# ESP-D1-mini-mainboard.net
KiCad netlist of a schematic drawn in EAGLE
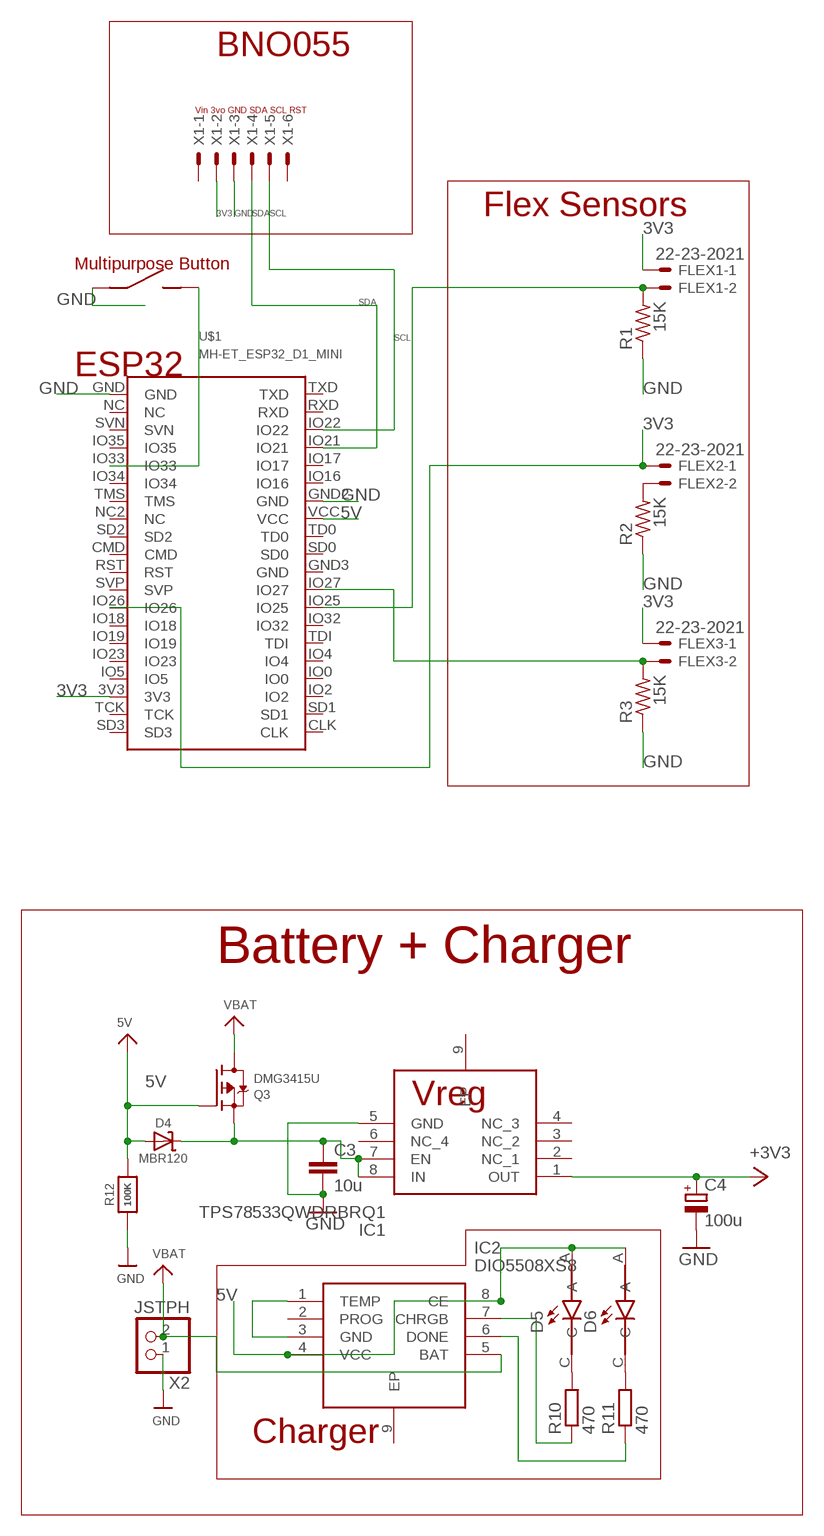
[diagram p0: schematic, sheet 1]

(export (version "E")
  (design (tool "Eeschema 10.0.6"))
  (components
    (comp (ref "BTN2")
      (value "TS36CA-0.7")
      (footprint "eagle-import:SMD")
      (fields (field (name "MF") "SHOU HAN"))
      (libsource (lib "eagle-import") (part "TS36CA-0.7"))
    )
    (comp (ref "C3")
      (value "10u")
      (footprint "eagle-import:C0603")
      (libsource (lib "eagle-import") (part "C-EUC0603"))
    )
    (comp (ref "C4")
      (value "100u")
      (footprint "eagle-import:B_3528-21W")
      (libsource (lib "eagle-import") (part "CPOL-EUB/3528-21W"))
    )
    (comp (ref "D4")
      (value "MBR120")
      (footprint "eagle-import:SOD-123")
      (libsource (lib "eagle-import") (part "DIODE-SCHOTTKYSOD-123"))
    )
    (comp (ref "D5")
      (value "GREEN")
      (footprint "eagle-import:LEDC2012X70N")
      (fields (field (name "MF") "Dialight") (field (name "MP") "597-5311-402F"))
      (libsource (lib "eagle-import") (part "597-5311-402F"))
    )
    (comp (ref "D6")
      (value "GREEN")
      (footprint "eagle-import:LEDC2012X70N")
      (fields (field (name "MF") "Dialight") (field (name "MP") "597-5311-402F"))
      (libsource (lib "eagle-import") (part "597-5311-402F"))
    )
    (comp (ref "FLEX1")
      (value "22-23-2021")
      (footprint "eagle-import:22-23-2021")
      (fields (field (name "MF") "MOLEX"))
      (libsource (lib "eagle-import") (part "22-23-2021"))
    )
    (comp (ref "FLEX2")
      (value "22-23-2021")
      (footprint "eagle-import:22-23-2021")
      (fields (field (name "MF") "MOLEX"))
      (libsource (lib "eagle-import") (part "22-23-2021"))
    )
    (comp (ref "FLEX3")
      (value "22-23-2021")
      (footprint "eagle-import:22-23-2021")
      (fields (field (name "MF") "MOLEX"))
      (libsource (lib "eagle-import") (part "22-23-2021"))
    )
    (comp (ref "IC1")
      (value "TPS78533QWDRBRQ1")
      (footprint "eagle-import:SON65P300X300X100-9N")
      (fields (field (name "MOUSER_PART_NUMBER") "595-TPS78533QWDRBRQ1"))
      (libsource (lib "eagle-import") (part "TPS78533QWDRBRQ1"))
    )
    (comp (ref "IC2")
      (value "DIO5508XS8")
      (footprint "eagle-import:SOIC127P600X170-9N")
      (fields (field (name "MOUSER_PART_NUMBER") "453-DIO5508XS8"))
      (libsource (lib "eagle-import") (part "DIO5508XS8"))
    )
    (comp (ref "Q3")
      (value "DMG3415U")
      (footprint "eagle-import:SOT23-R")
      (libsource (lib "eagle-import") (part "MOSFET-P"))
    )
    (comp (ref "R1")
      (value "15K")
      (footprint "eagle-import:0805-THM")
      (libsource (lib "eagle-import") (part "FLIPFLOP-RES"))
    )
    (comp (ref "R2")
      (value "15K")
      (footprint "eagle-import:0805-THM")
      (libsource (lib "eagle-import") (part "FLIPFLOP-RES"))
    )
    (comp (ref "R3")
      (value "15K")
      (footprint "eagle-import:0805-THM")
      (libsource (lib "eagle-import") (part "FLIPFLOP-RES"))
    )
    (comp (ref "R10")
      (value "470")
      (footprint "eagle-import:R0603")
      (libsource (lib "eagle-import") (part "R-EU_R0603"))
    )
    (comp (ref "R11")
      (value "470")
      (footprint "eagle-import:R0603")
      (libsource (lib "eagle-import") (part "R-EU_R0603"))
    )
    (comp (ref "R12")
      (value "100K")
      (footprint "eagle-import:0603-NO")
      (libsource (lib "eagle-import") (part "RESISTOR_0603_NOOUT"))
    )
    (comp (ref "U$1")
      (value "MH-ET_ESP32_D1_MINI")
      (footprint "eagle-import:MH-ET_ESP32_D1_MINI")
      (libsource (lib "eagle-import") (part "MH-ET_ESP32_D1_MINI"))
    )
    (comp (ref "X1")
      (value "22-23-2061")
      (footprint "eagle-import:22-23-2061")
      (fields (field (name "MF") "MOLEX"))
      (libsource (lib "eagle-import") (part "22-23-2061"))
    )
    (comp (ref "X2")
      (value "JSTPH")
      (footprint "eagle-import:JSTPH2")
      (libsource (lib "eagle-import") (part "CON_JST_PH_2PIN"))
    )
  )
  (nets
    (net (code "1") (name "+3V3") (class "Default")
      (node (ref "C4") (pin "+") (pinfunction "+_+") (pintype "passive"))
      (node (ref "IC1") (pin "1") (pinfunction "OUT_1") (pintype "bidirectional"))
    )
    (net (code "2") (name "/3V3") (class "Default")
      (node (ref "FLEX1") (pin "1") (pinfunction "S_1") (pintype "passive"))
      (node (ref "FLEX2") (pin "1") (pinfunction "S_1") (pintype "passive"))
      (node (ref "FLEX3") (pin "1") (pinfunction "S_1") (pintype "passive"))
      (node (ref "U$1") (pin "3V3") (pinfunction "3V3_3V3") (pintype "bidirectional"))
      (node (ref "U$1") (pin "IO26") (pinfunction "IO26_IO26") (pintype "bidirectional"))
      (node (ref "X1") (pin "2") (pinfunction "S_2") (pintype "passive"))
    )
    (net (code "3") (name "/SCL") (class "Default")
      (node (ref "U$1") (pin "IO22") (pinfunction "IO22_IO22") (pintype "bidirectional"))
      (node (ref "X1") (pin "5") (pinfunction "S_5") (pintype "passive"))
    )
    (net (code "4") (name "/SDA") (class "Default")
      (node (ref "U$1") (pin "IO21") (pinfunction "IO21_IO21") (pintype "bidirectional"))
      (node (ref "X1") (pin "4") (pinfunction "S_4") (pintype "passive"))
    )
    (net (code "5") (name "5V") (class "Default")
      (node (ref "D4") (pin "A") (pinfunction "A_A") (pintype "passive"))
      (node (ref "D5") (pin "A") (pinfunction "A_A") (pintype "passive"))
      (node (ref "D6") (pin "A") (pinfunction "A_A") (pintype "passive"))
      (node (ref "IC2") (pin "4") (pinfunction "VCC_4") (pintype "bidirectional"))
      (node (ref "IC2") (pin "8") (pinfunction "CE_8") (pintype "bidirectional"))
      (node (ref "Q3") (pin "1") (pinfunction "G_1") (pintype "passive"))
      (node (ref "R12") (pin "2") (pinfunction "2_2") (pintype "passive"))
      (node (ref "U$1") (pin "VCC") (pinfunction "VCC_VCC") (pintype "bidirectional"))
    )
    (net (code "6") (name "GND") (class "Default")
      (node (ref "BTN2") (pin "A") (pinfunction "CASE_A") (pintype "power_in"))
      (node (ref "BTN2") (pin "B") (pinfunction "CASE_B") (pintype "power_in"))
      (node (ref "BTN2") (pin "C") (pinfunction "P$1_C") (pintype "bidirectional"))
      (node (ref "C3") (pin "2") (pinfunction "2_2") (pintype "passive"))
      (node (ref "C4") (pin "-") (pinfunction "-_-") (pintype "passive"))
      (node (ref "IC1") (pin "5") (pinfunction "GND_5") (pintype "bidirectional"))
      (node (ref "R1") (pin "1") (pinfunction "1_1") (pintype "passive"))
      (node (ref "R12") (pin "1") (pinfunction "1_1") (pintype "passive"))
      (node (ref "R2") (pin "1") (pinfunction "1_1") (pintype "passive"))
      (node (ref "R3") (pin "1") (pinfunction "1_1") (pintype "passive"))
      (node (ref "U$1") (pin "GND") (pinfunction "GND_GND") (pintype "bidirectional"))
      (node (ref "U$1") (pin "GND2") (pinfunction "GND_GND2") (pintype "bidirectional"))
      (node (ref "X1") (pin "3") (pinfunction "S_3") (pintype "passive"))
      (node (ref "X2") (pin "1") (pinfunction "1_1") (pintype "passive"))
    )
    (net (code "7") (name "Net-(BTN2-P$2)") (class "Default")
      (node (ref "BTN2") (pin "D") (pinfunction "P$2_D") (pintype "bidirectional"))
      (node (ref "U$1") (pin "IO33") (pinfunction "IO33_IO33") (pintype "bidirectional"))
    )
    (net (code "8") (name "Net-(D5-PadC)") (class "Default")
      (node (ref "D5") (pin "C") (pinfunction "C_C") (pintype "passive"))
      (node (ref "R10") (pin "2") (pinfunction "2_2") (pintype "passive"))
    )
    (net (code "9") (name "Net-(D6-PadC)") (class "Default")
      (node (ref "D6") (pin "C") (pinfunction "C_C") (pintype "passive"))
      (node (ref "R11") (pin "2") (pinfunction "2_2") (pintype "passive"))
    )
    (net (code "10") (name "Net-(FLEX1B-S)") (class "Default")
      (node (ref "FLEX1") (pin "2") (pinfunction "S_2") (pintype "passive"))
      (node (ref "R1") (pin "2") (pinfunction "2_2") (pintype "passive"))
      (node (ref "U$1") (pin "IO25") (pinfunction "IO25_IO25") (pintype "bidirectional"))
    )
    (net (code "11") (name "Net-(FLEX2B-S)") (class "Default")
      (node (ref "FLEX2") (pin "2") (pinfunction "S_2") (pintype "passive"))
      (node (ref "R2") (pin "2") (pinfunction "2_2") (pintype "passive"))
    )
    (net (code "12") (name "Net-(FLEX3B-S)") (class "Default")
      (node (ref "FLEX3") (pin "2") (pinfunction "S_2") (pintype "passive"))
      (node (ref "R3") (pin "2") (pinfunction "2_2") (pintype "passive"))
      (node (ref "U$1") (pin "IO27") (pinfunction "IO27_IO27") (pintype "bidirectional"))
    )
    (net (code "13") (name "Net-(IC1-EN)") (class "Default")
      (node (ref "C3") (pin "1") (pinfunction "1_1") (pintype "passive"))
      (node (ref "D4") (pin "C") (pinfunction "C_C") (pintype "passive"))
      (node (ref "IC1") (pin "7") (pinfunction "EN_7") (pintype "bidirectional"))
      (node (ref "IC1") (pin "8") (pinfunction "IN_8") (pintype "bidirectional"))
      (node (ref "Q3") (pin "2") (pinfunction "S_2") (pintype "passive"))
    )
    (net (code "14") (name "Net-(IC2-CHRGB)") (class "Default")
      (node (ref "IC2") (pin "7") (pinfunction "CHRGB_7") (pintype "bidirectional"))
      (node (ref "R10") (pin "1") (pinfunction "1_1") (pintype "passive"))
    )
    (net (code "15") (name "Net-(IC2-DONE)") (class "Default")
      (node (ref "IC2") (pin "6") (pinfunction "DONE_6") (pintype "bidirectional"))
      (node (ref "R11") (pin "1") (pinfunction "1_1") (pintype "passive"))
    )
    (net (code "16") (name "Net-(IC2-GND)") (class "Default")
      (node (ref "IC2") (pin "1") (pinfunction "TEMP_1") (pintype "bidirectional"))
      (node (ref "IC2") (pin "3") (pinfunction "GND_3") (pintype "bidirectional"))
    )
    (net (code "17") (name "VBAT") (class "Default")
      (node (ref "IC2") (pin "5") (pinfunction "BAT_5") (pintype "bidirectional"))
      (node (ref "Q3") (pin "3") (pinfunction "D_3") (pintype "passive"))
      (node (ref "X2") (pin "2") (pinfunction "2_2") (pintype "passive"))
    )
    (net (code "18") (name "unconnected-(IC1-EP-Pad9)") (class "Default")
      (node (ref "IC1") (pin "9") (pinfunction "EP_9") (pintype "bidirectional"))
    )
    (net (code "19") (name "unconnected-(IC1-NC_1-Pad2)") (class "Default")
      (node (ref "IC1") (pin "2") (pinfunction "NC_1_2") (pintype "bidirectional"))
    )
    (net (code "20") (name "unconnected-(IC1-NC_2-Pad3)") (class "Default")
      (node (ref "IC1") (pin "3") (pinfunction "NC_2_3") (pintype "bidirectional"))
    )
    (net (code "21") (name "unconnected-(IC1-NC_3-Pad4)") (class "Default")
      (node (ref "IC1") (pin "4") (pinfunction "NC_3_4") (pintype "bidirectional"))
    )
    (net (code "22") (name "unconnected-(IC1-NC_4-Pad6)") (class "Default")
      (node (ref "IC1") (pin "6") (pinfunction "NC_4_6") (pintype "bidirectional"))
    )
    (net (code "23") (name "unconnected-(IC2-EP-Pad9)") (class "Default")
      (node (ref "IC2") (pin "9") (pinfunction "EP_9") (pintype "bidirectional"))
    )
    (net (code "24") (name "unconnected-(IC2-PROG-Pad2)") (class "Default")
      (node (ref "IC2") (pin "2") (pinfunction "PROG_2") (pintype "bidirectional"))
    )
    (net (code "25") (name "unconnected-(U$1-GND-PadGND3)") (class "Default")
      (node (ref "U$1") (pin "GND3") (pinfunction "GND_GND3") (pintype "bidirectional"))
    )
    (net (code "26") (name "unconnected-(U$1-NC-PadNC2)") (class "Default")
      (node (ref "U$1") (pin "NC2") (pinfunction "NC_NC2") (pintype "bidirectional"))
    )
    (net (code "27") (name "unconnected-(U$1-PadCLK)") (class "Default")
      (node (ref "U$1") (pin "CLK") (pinfunction "CLK_CLK") (pintype "bidirectional"))
    )
    (net (code "28") (name "unconnected-(U$1-PadCMD)") (class "Default")
      (node (ref "U$1") (pin "CMD") (pinfunction "CMD_CMD") (pintype "bidirectional"))
    )
    (net (code "29") (name "unconnected-(U$1-PadIO0)") (class "Default")
      (node (ref "U$1") (pin "IO0") (pinfunction "IO0_IO0") (pintype "bidirectional"))
    )
    (net (code "30") (name "unconnected-(U$1-PadIO2)") (class "Default")
      (node (ref "U$1") (pin "IO2") (pinfunction "IO2_IO2") (pintype "bidirectional"))
    )
    (net (code "31") (name "unconnected-(U$1-PadIO4)") (class "Default")
      (node (ref "U$1") (pin "IO4") (pinfunction "IO4_IO4") (pintype "bidirectional"))
    )
    (net (code "32") (name "unconnected-(U$1-PadIO5)") (class "Default")
      (node (ref "U$1") (pin "IO5") (pinfunction "IO5_IO5") (pintype "bidirectional"))
    )
    (net (code "33") (name "unconnected-(U$1-PadIO16)") (class "Default")
      (node (ref "U$1") (pin "IO16") (pinfunction "IO16_IO16") (pintype "bidirectional"))
    )
    (net (code "34") (name "unconnected-(U$1-PadIO17)") (class "Default")
      (node (ref "U$1") (pin "IO17") (pinfunction "IO17_IO17") (pintype "bidirectional"))
    )
    (net (code "35") (name "unconnected-(U$1-PadIO18)") (class "Default")
      (node (ref "U$1") (pin "IO18") (pinfunction "IO18_IO18") (pintype "bidirectional"))
    )
    (net (code "36") (name "unconnected-(U$1-PadIO19)") (class "Default")
      (node (ref "U$1") (pin "IO19") (pinfunction "IO19_IO19") (pintype "bidirectional"))
    )
    (net (code "37") (name "unconnected-(U$1-PadIO23)") (class "Default")
      (node (ref "U$1") (pin "IO23") (pinfunction "IO23_IO23") (pintype "bidirectional"))
    )
    (net (code "38") (name "unconnected-(U$1-PadIO32)") (class "Default")
      (node (ref "U$1") (pin "IO32") (pinfunction "IO32_IO32") (pintype "bidirectional"))
    )
    (net (code "39") (name "unconnected-(U$1-PadIO34)") (class "Default")
      (node (ref "U$1") (pin "IO34") (pinfunction "IO34_IO34") (pintype "bidirectional"))
    )
    (net (code "40") (name "unconnected-(U$1-PadIO35)") (class "Default")
      (node (ref "U$1") (pin "IO35") (pinfunction "IO35_IO35") (pintype "bidirectional"))
    )
    (net (code "41") (name "unconnected-(U$1-PadNC)") (class "Default")
      (node (ref "U$1") (pin "NC") (pinfunction "NC_NC") (pintype "bidirectional"))
    )
    (net (code "42") (name "unconnected-(U$1-PadRST)") (class "Default")
      (node (ref "U$1") (pin "RST") (pinfunction "RST_RST") (pintype "bidirectional"))
    )
    (net (code "43") (name "unconnected-(U$1-PadRXD)") (class "Default")
      (node (ref "U$1") (pin "RXD") (pinfunction "RXD_RXD") (pintype "bidirectional"))
    )
    (net (code "44") (name "unconnected-(U$1-PadSD0)") (class "Default")
      (node (ref "U$1") (pin "SD0") (pinfunction "SD0_SD0") (pintype "bidirectional"))
    )
    (net (code "45") (name "unconnected-(U$1-PadSD1)") (class "Default")
      (node (ref "U$1") (pin "SD1") (pinfunction "SD1_SD1") (pintype "bidirectional"))
    )
    (net (code "46") (name "unconnected-(U$1-PadSD2)") (class "Default")
      (node (ref "U$1") (pin "SD2") (pinfunction "SD2_SD2") (pintype "bidirectional"))
    )
    (net (code "47") (name "unconnected-(U$1-PadSD3)") (class "Default")
      (node (ref "U$1") (pin "SD3") (pinfunction "SD3_SD3") (pintype "bidirectional"))
    )
    (net (code "48") (name "unconnected-(U$1-PadSVN)") (class "Default")
      (node (ref "U$1") (pin "SVN") (pinfunction "SVN_SVN") (pintype "bidirectional"))
    )
    (net (code "49") (name "unconnected-(U$1-PadSVP)") (class "Default")
      (node (ref "U$1") (pin "SVP") (pinfunction "SVP_SVP") (pintype "bidirectional"))
    )
    (net (code "50") (name "unconnected-(U$1-PadTCK)") (class "Default")
      (node (ref "U$1") (pin "TCK") (pinfunction "TCK_TCK") (pintype "bidirectional"))
    )
    (net (code "51") (name "unconnected-(U$1-PadTD0)") (class "Default")
      (node (ref "U$1") (pin "TD0") (pinfunction "TD0_TD0") (pintype "bidirectional"))
    )
    (net (code "52") (name "unconnected-(U$1-PadTDI)") (class "Default")
      (node (ref "U$1") (pin "TDI") (pinfunction "TDI_TDI") (pintype "bidirectional"))
    )
    (net (code "53") (name "unconnected-(U$1-PadTMS)") (class "Default")
      (node (ref "U$1") (pin "TMS") (pinfunction "TMS_TMS") (pintype "bidirectional"))
    )
    (net (code "54") (name "unconnected-(U$1-PadTXD)") (class "Default")
      (node (ref "U$1") (pin "TXD") (pinfunction "TXD_TXD") (pintype "bidirectional"))
    )
    (net (code "55") (name "unconnected-(X1A-S-Pad1)") (class "Default")
      (node (ref "X1") (pin "1") (pinfunction "S_1") (pintype "passive"))
    )
    (net (code "56") (name "unconnected-(X1F-S-Pad6)") (class "Default")
      (node (ref "X1") (pin "6") (pinfunction "S_6") (pintype "passive"))
    )
  )
)
